# Sense_5_Signal_Isolation.net
KiCad netlist of a schematic drawn in Altium Designer
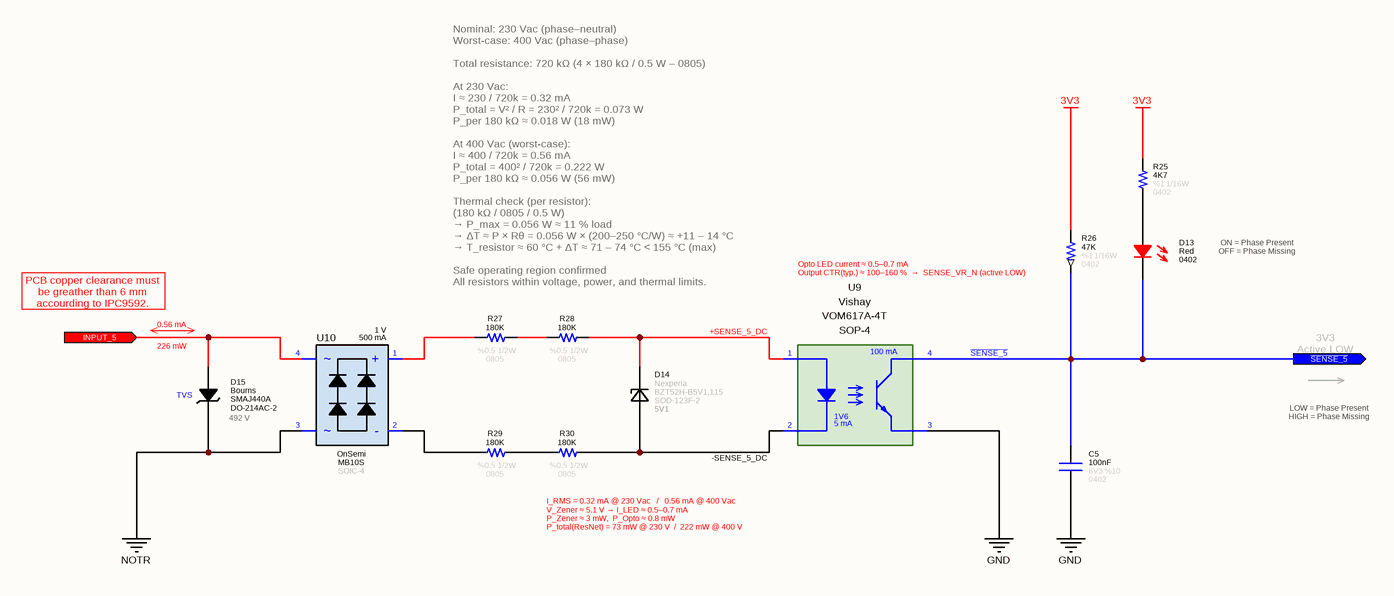
[diagram p0: Sense 5 Signal Isolation.SchDoc]

(export (version "E")
  (design (tool "Eeschema 10.0.6"))
  (components
    (comp (ref "C5")
      (value "100nF")
      (footprint "CAPACITOR_0402")
      (description "Capacitor (MLCC) - 100nF / 6V3 / 0402")
      (fields
        (field (name "MANUFACTURER PART NUMBER") "04026D104KAT4A")
        (field (name "TOLERANCE") "%10")
        (field (name "VOLTAGE") "6V3")
        (field (name "CASE") "0402")
        (field (name "Comment") "Capacitor - 100nF [0402] (MLCC)")
      )
      (libsource (lib "Akkoyun") (part "Capacitor - 100nF [0402-6V3]"))
    )
    (comp (ref "D13")
      (value "SMD LED (Red)")
      (footprint "LED_0402")
      (description "Standard LEDs - SMD MINI-MOLD ULTRA COMPACT RED")
      (fields
        (field (name "MANUFACTURER PART NUMBER") "SML-P12VTT86R")
        (field (name "CASE") "0402")
        (field (name "COLOR") "Red")
      )
      (libsource (lib "Akkoyun") (part "Diode - LED (0402-Red)"))
    )
    (comp (ref "D14")
      (value "BZT52H-B5V1,115")
      (footprint "SOD-123F-2")
      (description "Zener Diodes BZT52H-B5V1/SOD123F/SOD2")
      (fields
        (field (name "ZENER VOLTAGE") "5V1")
        (field (name "MANUFACTURER NAME") "Nexperia")
        (field (name "MANUFACTURER PART NUMBER") "BZT52H-B5V1,115")
        (field (name "CASE") "SOD-123F-2")
      )
      (libsource (lib "Akkoyun") (part "Diode - BZT52H-B5V1,115"))
    )
    (comp (ref "D15")
      (value "SMAJ440A")
      (footprint "DO-220AA-2")
      (description "ESD Protection Diodes / TVS Diodes 440volts 1uA .6 Amps Uni-Dir")
      (fields
        (field (name "BREAKDOWN VOLTAGE") "492 V")
        (field (name "MANUFACTURER NAME") "Bourns")
        (field (name "MANUFACTURER PART NUMBER") "SMAJ440A")
        (field (name "CASE") "DO-214AC-2")
      )
      (libsource (lib "Akkoyun") (part "Diode - SMAJ440A (TVS)"))
    )
    (comp (ref "R25")
      (value "4K7")
      (footprint "RESISTOR_0402")
      (description "Thick Film Resistors - SMD 1/16 W 4.7 KOhm 1%")
      (fields
        (field (name "MANUFACTURER PART NUMBER") "CRCW04024K70FKED")
        (field (name "TOLERANCE") "%1")
        (field (name "CASE") "0402")
        (field (name "POWER") "1/16W")
        (field (name "Comment") "4K7 - 0402 - %1 - 1/16W")
      )
      (libsource (lib "Akkoyun") (part "Resistor - 4K7 [0402]"))
    )
    (comp (ref "R26")
      (value "47K")
      (footprint "RESISTOR_0402")
      (description "Thick Film Resistors - SMD 1/16 W 47 KOhm 1%")
      (fields
        (field (name "MANUFACTURER PART NUMBER") "CRCW040247K0FKED")
        (field (name "TOLERANCE") "%1")
        (field (name "CASE") "0402")
        (field (name "POWER") "1/16W")
        (field (name "Comment") "47K - 0402 - %1 - 1/16W")
      )
      (libsource (lib "Akkoyun") (part "Resistor - 47K [0402]"))
    )
    (comp (ref "R27")
      (value "180K")
      (footprint "RESISTOR_0805")
      (description "Thick Film Resistors - SMD 0805 180Kohms 0.5W 0.5% AEC-Q200")
      (fields
        (field (name "MANUFACTURER PART NUMBER") "ERJ-P06D1803V")
        (field (name "TOLERANCE") "%0.5")
        (field (name "CASE") "0805")
        (field (name "POWER") "1/2W")
        (field (name "Comment") "180K - 0805 - %0.5 - 1/2W")
      )
      (libsource (lib "Akkoyun") (part "Resistor - 180K [0805]"))
    )
    (comp (ref "R28")
      (value "180K")
      (footprint "RESISTOR_0805")
      (description "Thick Film Resistors - SMD 0805 180Kohms 0.5W 0.5% AEC-Q200")
      (fields
        (field (name "MANUFACTURER PART NUMBER") "ERJ-P06D1803V")
        (field (name "TOLERANCE") "%0.5")
        (field (name "CASE") "0805")
        (field (name "POWER") "1/2W")
        (field (name "Comment") "180K - 0805 - %0.5 - 1/2W")
      )
      (libsource (lib "Akkoyun") (part "Resistor - 180K [0805]"))
    )
    (comp (ref "R29")
      (value "180K")
      (footprint "RESISTOR_0805")
      (description "Thick Film Resistors - SMD 0805 180Kohms 0.5W 0.5% AEC-Q200")
      (fields
        (field (name "MANUFACTURER PART NUMBER") "ERJ-P06D1803V")
        (field (name "TOLERANCE") "%0.5")
        (field (name "CASE") "0805")
        (field (name "POWER") "1/2W")
        (field (name "Comment") "180K - 0805 - %0.5 - 1/2W")
      )
      (libsource (lib "Akkoyun") (part "Resistor - 180K [0805]"))
    )
    (comp (ref "R30")
      (value "180K")
      (footprint "RESISTOR_0805")
      (description "Thick Film Resistors - SMD 0805 180Kohms 0.5W 0.5% AEC-Q200")
      (fields
        (field (name "MANUFACTURER PART NUMBER") "ERJ-P06D1803V")
        (field (name "TOLERANCE") "%0.5")
        (field (name "CASE") "0805")
        (field (name "POWER") "1/2W")
        (field (name "Comment") "180K - 0805 - %0.5 - 1/2W")
      )
      (libsource (lib "Akkoyun") (part "Resistor - 180K [0805]"))
    )
    (comp (ref "U9")
      (value "VOM617A-4T")
      (footprint "SOP-4V2")
      (description "Transistor Output Optocouplers Phototransistor Out CTR 160-320% 5mA")
      (fields
        (field (name "MANUFACTURER PART NUMBER") "VOM617A-4T")
        (field (name "MANUFACTURER NAME") "Vishay")
        (field (name "CASE") "SOP-4")
        (field (name "IF - FORWARD CURRENT") "5 mA")
        (field (name "VF - FORWARD VOLTAGE") "1V6")
        (field (name "MAXIMUM COLLECTOR CURRENT") "100 mA")
      )
      (libsource (lib "Akkoyun") (part "IC - VOM617A"))
    )
    (comp (ref "U10")
      (value "LTV-846S")
      (footprint "SOIC-4")
      (description "Transistor Output Optocouplers Optocplr Phototrans 4-Channel")
      (fields
        (field (name "IF - FORWARD CURRENT") "500 mA")
        (field (name "VF - FORWARD VOLTAGE") "1 V")
        (field (name "MANUFACTURER NAME") "OnSemi")
        (field (name "MANUFACTURER PART NUMBER") "MB10S")
        (field (name "CASE") "SOIC-4")
      )
      (libsource (lib "Akkoyun") (part "IC - MB10S"))
    )
  )
  (nets
    (net (code "1") (name "/+SENSE_5_DC") (class "Default")
      (node (ref "D14") (pin "1") (pinfunction "Cathode_1") (pintype "passive"))
      (node (ref "R28") (pin "1") (pinfunction "1_1") (pintype "passive"))
      (node (ref "U9") (pin "1") (pinfunction "LED_Anode_1") (pintype "passive"))
    )
    (net (code "2") (name "/-SENSE_5_DC") (class "Default")
      (node (ref "D14") (pin "2") (pinfunction "Anode_2") (pintype "passive"))
      (node (ref "R30") (pin "1") (pinfunction "1_1") (pintype "passive"))
      (node (ref "U9") (pin "2") (pinfunction "LED_Cathode_2") (pintype "passive"))
    )
    (net (code "3") (name "/INPUT_5") (class "Default")
      (node (ref "D15") (pin "1") (pinfunction "Anode_1") (pintype "passive"))
      (node (ref "U10") (pin "4") (pinfunction "~_4") (pintype "passive"))
    )
    (net (code "4") (name "/~{SENSE_5}") (class "Default")
      (node (ref "C5") (pin "2") (pinfunction "2_2") (pintype "passive"))
      (node (ref "D13") (pin "1") (pinfunction "1_1") (pintype "passive"))
      (node (ref "R26") (pin "1") (pinfunction "1_1") (pintype "output"))
      (node (ref "U9") (pin "4") (pinfunction "Collector_4") (pintype "passive"))
    )
    (net (code "5") (name "3V3") (class "Default")
      (node (ref "R25") (pin "2") (pinfunction "2_2") (pintype "passive"))
      (node (ref "R26") (pin "2") (pinfunction "2_2") (pintype "passive"))
    )
    (net (code "6") (name "GND") (class "Default")
      (node (ref "C5") (pin "1") (pinfunction "1_1") (pintype "passive"))
      (node (ref "U9") (pin "3") (pinfunction "Emiter_3") (pintype "passive"))
    )
    (net (code "7") (name "NOTR") (class "Default")
      (node (ref "D15") (pin "2") (pinfunction "Cathode_2") (pintype "passive"))
      (node (ref "U10") (pin "3") (pinfunction "~_3") (pintype "passive"))
    )
    (net (code "8") (name "Net-(D13-Pad2)") (class "Default")
      (node (ref "D13") (pin "2") (pinfunction "2_2") (pintype "passive"))
      (node (ref "R25") (pin "1") (pinfunction "1_1") (pintype "passive"))
    )
    (net (code "9") (name "Net-(R27-Pad1)") (class "Default")
      (node (ref "R27") (pin "1") (pinfunction "1_1") (pintype "passive"))
      (node (ref "R28") (pin "2") (pinfunction "2_2") (pintype "passive"))
    )
    (net (code "10") (name "Net-(R29-Pad1)") (class "Default")
      (node (ref "R29") (pin "1") (pinfunction "1_1") (pintype "passive"))
      (node (ref "R30") (pin "2") (pinfunction "2_2") (pintype "passive"))
    )
    (net (code "11") (name "Net-(U10-+)") (class "Default")
      (node (ref "R27") (pin "2") (pinfunction "2_2") (pintype "passive"))
      (node (ref "U10") (pin "1") (pinfunction "+_1") (pintype "passive"))
    )
    (net (code "12") (name "Net-(U10--)") (class "Default")
      (node (ref "R29") (pin "2") (pinfunction "2_2") (pintype "passive"))
      (node (ref "U10") (pin "2") (pinfunction "-_2") (pintype "passive"))
    )
  )
)
